# ESP8266.net
KiCad netlist of a schematic drawn in Altium Designer
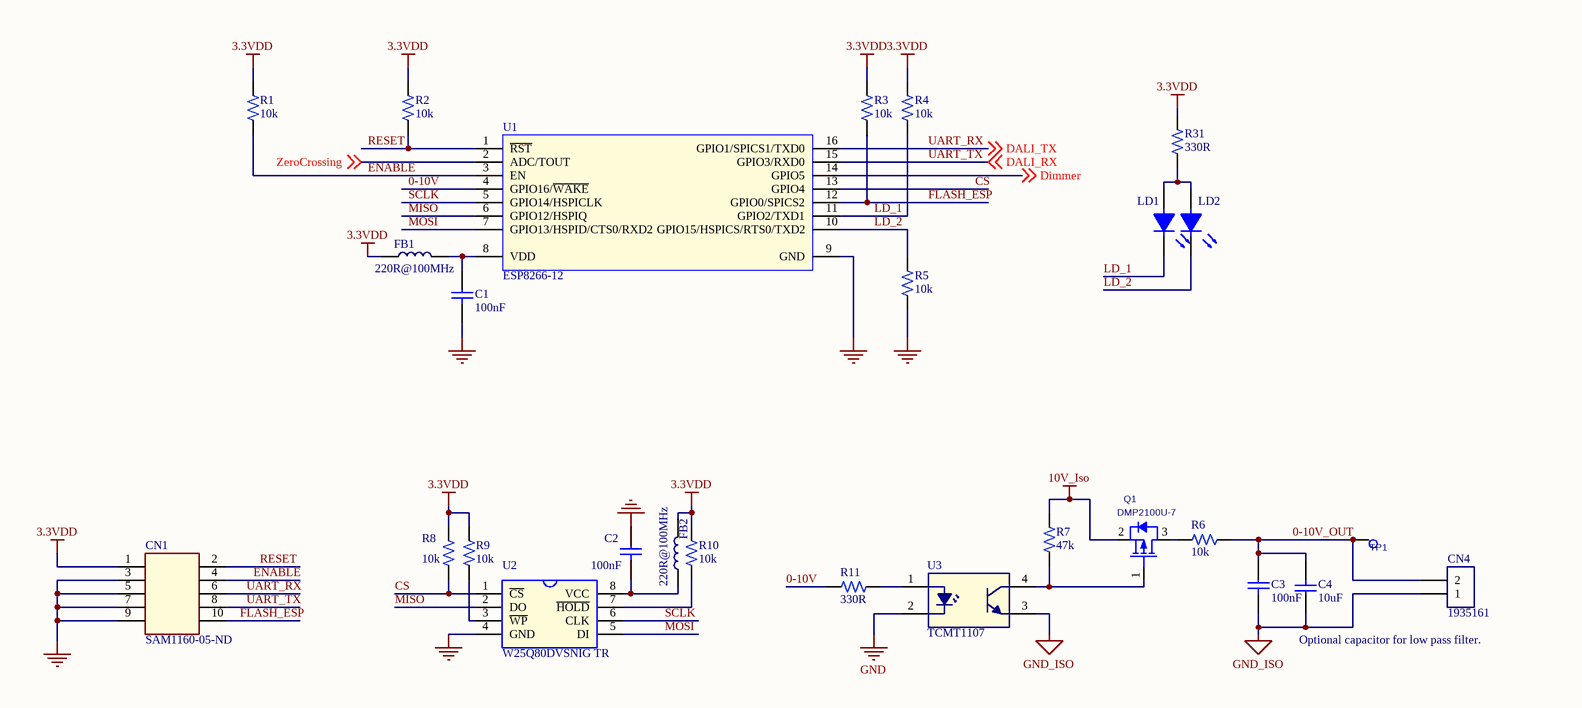
[diagram p0: ESP8266.SchDoc]

(export (version "E")
  (design (tool "Eeschema 10.0.6"))
  (components
    (comp (ref "C1")
      (value "100nF")
      (footprint "0603-3D")
      (description "CAP CER 0.1UF 50V 10% X7R 0603")
      (fields (field (name "VOLTAGE") "50V") (field (name "USER") "Anderson Daniel Soares"))
      (libsource (lib "CapacitoresPrjLib") (part "0.1uF 10% 0603 MLCC X7R 50V"))
    )
    (comp (ref "C2")
      (value "100nF")
      (footprint "0603-3D")
      (description "CAP CER 0.1UF 50V 10% X7R 0603")
      (fields (field (name "VOLTAGE") "50V") (field (name "USER") "Anderson Daniel Soares"))
      (libsource (lib "CapacitoresPrjLib") (part "0.1uF 10% 0603 MLCC X7R 50V"))
    )
    (comp (ref "C3")
      (value "100nF")
      (footprint "0603-3D")
      (description "CAP CER 0.1UF 50V 10% X7R 0603")
      (fields (field (name "VOLTAGE") "50V") (field (name "USER") "Anderson Daniel Soares"))
      (libsource (lib "CapacitoresPrjLib") (part "0.1uF 10% 0603 MLCC X7R 50V"))
    )
    (comp (ref "C4")
      (value "10uF")
      (footprint "CAP-0603-3D")
      (description "CAP CER 10UF 16V 20% X5R 0603")
      (fields (field (name "VOLTAGE") "16V") (field (name "USER") "Mateus Elias"))
      (libsource (lib "CapacitoresPrjLib") (part "10uF 20% 0603 MLCC X5R 16V"))
    )
    (comp (ref "CN1")
      (value "SAM1160-05-ND")
      (footprint "CON-SMD-MINITEK-H-2X5-127P")
      (description "10 Positions Header, Unshrouded Connector 0.050\" (1.27mm) Surface Mount, Right Angle Gold")
      (fields (field (name "USER") "Jean Pierre"))
      (libsource (lib "Conectores") (part "SAM1160-05-ND CN HDR 5X2 1.27mm 90°"))
    )
    (comp (ref "CN4")
      (value "1935161")
      (footprint "TERM BLOCK PCB 2POS 5.0MM")
      (description "TERM BLOCK PCB 2POS 5.0MM")
      (fields (field (name "USER") "Rodrigo Balbi"))
      (libsource (lib "Conectores") (part "1935161  TERM BLOCK PCB 2X1"))
    )
    (comp (ref "FB1")
      (value "220R@100MHz")
      (footprint "IND-0603-3D")
      (description "FERRITE CHIP 0603 220 OHM")
      (fields (field (name "USER") "Jean Pierre"))
      (libsource (lib "IndutoresPrjLib") (part "220R@100MHz 0603 FB 0.05R 2A"))
    )
    (comp (ref "FB2")
      (value "220R@100MHz")
      (footprint "IND-0603-3D")
      (description "FERRITE CHIP 0603 220 OHM")
      (fields (field (name "USER") "Jean Pierre"))
      (libsource (lib "IndutoresPrjLib") (part "220R@100MHz 0603 FB 0.05R 2A"))
    )
    (comp (ref "LD1")
      (value "LG R971-KN-1")
      (footprint "GREEN-LED-0805-3D")
      (description "Green 570nm LED Indication - Discrete 2.2V 0805 (2012 Metric)")
      (fields (field (name "USER") "Reis"))
      (libsource (lib "Opticos") (part "LED GREEN DIFFUSED 0805 SMD"))
    )
    (comp (ref "LD2")
      (value "LS R976-NR-1")
      (footprint "RED-LED-0805-3D")
      (description "Red 633nm LED Indication - Discrete 2V 0805 (2012 Metric)")
      (fields (field (name "USER") "Reis"))
      (libsource (lib "Opticos") (part "LED RED DIFFUSED 0805 SMD"))
    )
    (comp (ref "Q1")
      (value "DMP2100U-7")
      (footprint "SOT23-3D")
      (description "MOSFET P CH 20V 4.3A SOT23")
      (fields (field (name "USER") "Reis"))
      (libsource (lib "Transistores") (part "DMP2100U-7 MOSFET P-CH"))
    )
    (comp (ref "R1")
      (value "10k")
      (footprint "0603-3D")
      (description "RES SMD 10K OHM 1% 1/10W 0603")
      (fields
        (field (name "MANUFACTURER") "Yageo")
        (field (name "MANUFACTURER PART NUMBER") "RC0603FR-0710KL")
        (field (name "USER") "Pedro Vilela")
      )
      (libsource (lib "ResitoresPrjLib") (part "10k 1% 0603 TNF 1/10W"))
    )
    (comp (ref "R2")
      (value "10k")
      (footprint "0603-3D")
      (description "RES SMD 10K OHM 1% 1/10W 0603")
      (fields
        (field (name "MANUFACTURER") "Yageo")
        (field (name "MANUFACTURER PART NUMBER") "RC0603FR-0710KL")
        (field (name "USER") "Pedro Vilela")
      )
      (libsource (lib "ResitoresPrjLib") (part "10k 1% 0603 TNF 1/10W"))
    )
    (comp (ref "R3")
      (value "10k")
      (footprint "0603-3D")
      (description "RES SMD 10K OHM 1% 1/10W 0603")
      (fields
        (field (name "MANUFACTURER") "Yageo")
        (field (name "MANUFACTURER PART NUMBER") "RC0603FR-0710KL")
        (field (name "USER") "Pedro Vilela")
      )
      (libsource (lib "ResitoresPrjLib") (part "10k 1% 0603 TNF 1/10W"))
    )
    (comp (ref "R4")
      (value "10k")
      (footprint "0603-3D")
      (description "RES SMD 10K OHM 1% 1/10W 0603")
      (fields
        (field (name "MANUFACTURER") "Yageo")
        (field (name "MANUFACTURER PART NUMBER") "RC0603FR-0710KL")
        (field (name "USER") "Pedro Vilela")
      )
      (libsource (lib "ResitoresPrjLib") (part "10k 1% 0603 TNF 1/10W"))
    )
    (comp (ref "R5")
      (value "10k")
      (footprint "0603-3D")
      (description "RES SMD 10K OHM 1% 1/10W 0603")
      (fields
        (field (name "MANUFACTURER") "Yageo")
        (field (name "MANUFACTURER PART NUMBER") "RC0603FR-0710KL")
        (field (name "USER") "Pedro Vilela")
      )
      (libsource (lib "ResitoresPrjLib") (part "10k 1% 0603 TNF 1/10W"))
    )
    (comp (ref "R6")
      (value "10k")
      (footprint "0603-3D")
      (description "RES SMD 10K OHM 1% 1/10W 0603")
      (fields
        (field (name "MANUFACTURER") "Yageo")
        (field (name "MANUFACTURER PART NUMBER") "RC0603FR-0710KL")
        (field (name "USER") "Pedro Vilela")
      )
      (libsource (lib "ResitoresPrjLib") (part "10k 1% 0603 TNF 1/10W"))
    )
    (comp (ref "R7")
      (value "47k")
      (footprint "0603-3D")
      (description "RES SMD 47K OHM 1% 1/10W 0603")
      (fields (field (name "USER") "Anderson Daniel Soares"))
      (libsource (lib "ResitoresPrjLib") (part "47k 1% 0603 TKF 1/16W"))
    )
    (comp (ref "R8")
      (value "10k")
      (footprint "0603-3D")
      (description "RES SMD 10K OHM 1% 1/10W 0603")
      (fields
        (field (name "MANUFACTURER") "Yageo")
        (field (name "MANUFACTURER PART NUMBER") "RC0603FR-0710KL")
        (field (name "USER") "Pedro Vilela")
      )
      (libsource (lib "ResitoresPrjLib") (part "10k 1% 0603 TNF 1/10W"))
    )
    (comp (ref "R9")
      (value "10k")
      (footprint "0603-3D")
      (description "RES SMD 10K OHM 1% 1/10W 0603")
      (fields
        (field (name "MANUFACTURER") "Yageo")
        (field (name "MANUFACTURER PART NUMBER") "RC0603FR-0710KL")
        (field (name "USER") "Pedro Vilela")
      )
      (libsource (lib "ResitoresPrjLib") (part "10k 1% 0603 TNF 1/10W"))
    )
    (comp (ref "R10")
      (value "10k")
      (footprint "0603-3D")
      (description "RES SMD 10K OHM 1% 1/10W 0603")
      (fields
        (field (name "MANUFACTURER") "Yageo")
        (field (name "MANUFACTURER PART NUMBER") "RC0603FR-0710KL")
        (field (name "USER") "Pedro Vilela")
      )
      (libsource (lib "ResitoresPrjLib") (part "10k 1% 0603 TNF 1/10W"))
    )
    (comp (ref "R11")
      (value "330R")
      (footprint "0603-3D")
      (description "RES SMD 330 OHM 5% 1/10W 0603")
      (fields (field (name "TOLERANCE") "5%") (field (name "USER") "Luiz F Siecola"))
      (libsource (lib "ResitoresPrjLib") (part "330R 5% 0603 TKF 1/10W"))
    )
    (comp (ref "R31")
      (value "330R")
      (footprint "0603-3D")
      (description "RES SMD 330 OHM 5% 1/10W 0603")
      (fields (field (name "TOLERANCE") "5%") (field (name "USER") "Luiz F Siecola"))
      (libsource (lib "ResitoresPrjLib") (part "330R 5% 0603 TKF 1/10W"))
    )
    (comp (ref "TP1")
      (value "MECH TESTPOINT 1mm")
      (footprint "Fiducial smd 1mm")
      (description "Fiducial")
      (fields (field (name "USER") "Larissa"))
      (libsource (lib "DiversosPrjLib") (part "MECH TESTPOINT 1mm"))
    )
    (comp (ref "U1")
      (value "ESP8266-12")
      (footprint "ESP8266-14-3D")
      (description "ESP8266 SMT MODULE")
      (fields (field (name "USER") "Ricardo Dias"))
      (libsource (lib "LES") (part "ESP8266-12 Wi-Fi Module"))
    )
    (comp (ref "U2")
      (value "W25Q80DVSNIG TR")
      (footprint "SOIC8-3D")
      (description "IC FLASH 8MBIT 104MHZ 8SOIC")
      (fields (field (name "USER") "Ricardo Dias"))
      (libsource (lib "LES") (part "W25Q80DVSNIG TR IC FLASH 8MBIT"))
    )
    (comp (ref "U3")
      (value "TCMT1107")
      (footprint "SOP4")
      (description "OPTOISOLATOR 3.75KV TRANS 4-SOP")
      (fields (field (name "USER") "Jean Pierre"))
      (libsource (lib "Opticos") (part "TCMT1107 OPTO TRANS"))
    )
  )
  (nets
    (net (code "1") (name "/0-10V") (class "Default")
      (node (ref "R11") (pin "1") (pinfunction "1_1") (pintype "passive"))
      (node (ref "U1") (pin "4") (pinfunction "GPIO16/~{WAKE}_4") (pintype "passive"))
    )
    (net (code "2") (name "/0-10V_OUT") (class "Default")
      (node (ref "C3") (pin "1") (pinfunction "1_1") (pintype "passive"))
      (node (ref "C4") (pin "2") (pinfunction "2_2") (pintype "passive"))
      (node (ref "CN4") (pin "2") (pinfunction "2_2") (pintype "passive"))
      (node (ref "R6") (pin "1") (pinfunction "1_1") (pintype "passive"))
      (node (ref "TP1") (pin "1") (pinfunction "1_1") (pintype "passive"))
    )
    (net (code "3") (name "/CS") (class "Default")
      (node (ref "R8") (pin "1") (pinfunction "1_1") (pintype "passive"))
      (node (ref "U1") (pin "13") (pinfunction "GPIO4_13") (pintype "passive"))
      (node (ref "U2") (pin "1") (pinfunction "~{CS}_1") (pintype "passive"))
    )
    (net (code "4") (name "/ENABLE") (class "Default")
      (node (ref "CN1") (pin "4") (pinfunction "4_4") (pintype "passive"))
      (node (ref "R1") (pin "1") (pinfunction "1_1") (pintype "passive"))
      (node (ref "U1") (pin "3") (pinfunction "EN_3") (pintype "passive"))
    )
    (net (code "5") (name "/FLASH_ESP") (class "Default")
      (node (ref "CN1") (pin "10") (pinfunction "10_10") (pintype "passive"))
      (node (ref "R3") (pin "1") (pinfunction "1_1") (pintype "passive"))
      (node (ref "U1") (pin "12") (pinfunction "GPIO0/SPICS2_12") (pintype "passive"))
    )
    (net (code "6") (name "/LD_1") (class "Default")
      (node (ref "LD1") (pin "2") (pinfunction "CATODE_2") (pintype "passive"))
      (node (ref "R4") (pin "1") (pinfunction "1_1") (pintype "passive"))
      (node (ref "U1") (pin "11") (pinfunction "GPIO2/TXD1_11") (pintype "passive"))
    )
    (net (code "7") (name "/LD_2") (class "Default")
      (node (ref "LD2") (pin "2") (pinfunction "CATODE_2") (pintype "passive"))
      (node (ref "R5") (pin "2") (pinfunction "2_2") (pintype "passive"))
      (node (ref "U1") (pin "10") (pinfunction "GPIO15/HSPICS/RTS0/TXD2_10") (pintype "passive"))
    )
    (net (code "8") (name "/MISO") (class "Default")
      (node (ref "U1") (pin "6") (pinfunction "GPIO12/HSPIQ_6") (pintype "passive"))
      (node (ref "U2") (pin "2") (pinfunction "DO_2") (pintype "passive"))
    )
    (net (code "9") (name "/MOSI") (class "Default")
      (node (ref "U1") (pin "7") (pinfunction "GPIO13/HSPID/CTS0/RXD2_7") (pintype "passive"))
      (node (ref "U2") (pin "5") (pinfunction "DI_5") (pintype "passive"))
    )
    (net (code "10") (name "/RESET") (class "Default")
      (node (ref "CN1") (pin "2") (pinfunction "2_2") (pintype "passive"))
      (node (ref "R2") (pin "1") (pinfunction "1_1") (pintype "passive"))
      (node (ref "U1") (pin "1") (pinfunction "~{RST}_1") (pintype "passive"))
    )
    (net (code "11") (name "/SCLK") (class "Default")
      (node (ref "U1") (pin "5") (pinfunction "GPIO14/HSPICLK_5") (pintype "passive"))
      (node (ref "U2") (pin "6") (pinfunction "CLK_6") (pintype "passive"))
    )
    (net (code "12") (name "3.3VDD") (class "Default")
      (node (ref "CN1") (pin "1") (pinfunction "1_1") (pintype "passive"))
      (node (ref "FB1") (pin "1") (pinfunction "1_1") (pintype "passive"))
      (node (ref "FB2") (pin "2") (pinfunction "2_2") (pintype "passive"))
      (node (ref "R1") (pin "2") (pinfunction "2_2") (pintype "passive"))
      (node (ref "R10") (pin "2") (pinfunction "2_2") (pintype "passive"))
      (node (ref "R2") (pin "2") (pinfunction "2_2") (pintype "passive"))
      (node (ref "R3") (pin "2") (pinfunction "2_2") (pintype "passive"))
      (node (ref "R31") (pin "2") (pinfunction "2_2") (pintype "passive"))
      (node (ref "R4") (pin "2") (pinfunction "2_2") (pintype "passive"))
      (node (ref "R8") (pin "2") (pinfunction "2_2") (pintype "passive"))
      (node (ref "R9") (pin "2") (pinfunction "2_2") (pintype "passive"))
    )
    (net (code "13") (name "10V_Iso") (class "Default")
      (node (ref "Q1") (pin "2") (pinfunction "S_2") (pintype "passive"))
      (node (ref "R7") (pin "2") (pinfunction "2_2") (pintype "passive"))
    )
    (net (code "14") (name "DALI_RX") (class "Default")
      (node (ref "CN1") (pin "8") (pinfunction "8_8") (pintype "passive"))
      (node (ref "U1") (pin "15") (pinfunction "GPIO3/RXD0_15") (pintype "passive"))
    )
    (net (code "15") (name "DALI_TX") (class "Default")
      (node (ref "CN1") (pin "6") (pinfunction "6_6") (pintype "passive"))
      (node (ref "U1") (pin "16") (pinfunction "GPIO1/SPICS1/TXD0_16") (pintype "passive"))
    )
    (net (code "16") (name "Dimmer") (class "Default")
      (node (ref "U1") (pin "14") (pinfunction "GPIO5_14") (pintype "passive"))
    )
    (net (code "17") (name "GND") (class "Default")
      (node (ref "C1") (pin "2") (pinfunction "2_2") (pintype "passive"))
      (node (ref "C2") (pin "1") (pinfunction "1_1") (pintype "passive"))
      (node (ref "CN1") (pin "3") (pinfunction "3_3") (pintype "passive"))
      (node (ref "CN1") (pin "5") (pinfunction "5_5") (pintype "passive"))
      (node (ref "CN1") (pin "7") (pinfunction "7_7") (pintype "passive"))
      (node (ref "CN1") (pin "9") (pinfunction "9_9") (pintype "passive"))
      (node (ref "R5") (pin "1") (pinfunction "1_1") (pintype "passive"))
      (node (ref "U1") (pin "9") (pinfunction "GND_9") (pintype "passive"))
      (node (ref "U2") (pin "4") (pinfunction "GND_4") (pintype "passive"))
      (node (ref "U3") (pin "2") (pinfunction "K_2") (pintype "passive"))
    )
    (net (code "18") (name "GND_ISO") (class "Default")
      (node (ref "C3") (pin "2") (pinfunction "2_2") (pintype "passive"))
      (node (ref "C4") (pin "1") (pinfunction "1_1") (pintype "passive"))
      (node (ref "CN4") (pin "1") (pinfunction "1_1") (pintype "passive"))
      (node (ref "U3") (pin "3") (pinfunction "E_3") (pintype "passive"))
    )
    (net (code "19") (name "Net-(LD1-ANODE)") (class "Default")
      (node (ref "LD1") (pin "1") (pinfunction "ANODE_1") (pintype "passive"))
      (node (ref "LD2") (pin "1") (pinfunction "ANODE_1") (pintype "passive"))
      (node (ref "R31") (pin "1") (pinfunction "1_1") (pintype "passive"))
    )
    (net (code "20") (name "Net-(Q1-D)") (class "Default")
      (node (ref "Q1") (pin "3") (pinfunction "D_3") (pintype "passive"))
      (node (ref "R6") (pin "2") (pinfunction "2_2") (pintype "passive"))
    )
    (net (code "21") (name "Net-(Q1-G)") (class "Default")
      (node (ref "Q1") (pin "1") (pinfunction "G_1") (pintype "passive"))
      (node (ref "R7") (pin "1") (pinfunction "1_1") (pintype "passive"))
      (node (ref "U3") (pin "4") (pinfunction "C_4") (pintype "passive"))
    )
    (net (code "22") (name "Net-(U1-VDD)") (class "Default")
      (node (ref "C1") (pin "1") (pinfunction "1_1") (pintype "passive"))
      (node (ref "FB1") (pin "2") (pinfunction "2_2") (pintype "passive"))
      (node (ref "U1") (pin "8") (pinfunction "VDD_8") (pintype "passive"))
    )
    (net (code "23") (name "Net-(U2-VCC)") (class "Default")
      (node (ref "C2") (pin "2") (pinfunction "2_2") (pintype "passive"))
      (node (ref "FB2") (pin "1") (pinfunction "1_1") (pintype "passive"))
      (node (ref "U2") (pin "8") (pinfunction "VCC_8") (pintype "passive"))
    )
    (net (code "24") (name "Net-(U2-~{HOLD})") (class "Default")
      (node (ref "R10") (pin "1") (pinfunction "1_1") (pintype "passive"))
      (node (ref "U2") (pin "7") (pinfunction "~{HOLD}_7") (pintype "passive"))
    )
    (net (code "25") (name "Net-(U2-~{WP})") (class "Default")
      (node (ref "R9") (pin "1") (pinfunction "1_1") (pintype "passive"))
      (node (ref "U2") (pin "3") (pinfunction "~{WP}_3") (pintype "passive"))
    )
    (net (code "26") (name "Net-(U3-A)") (class "Default")
      (node (ref "R11") (pin "2") (pinfunction "2_2") (pintype "passive"))
      (node (ref "U3") (pin "1") (pinfunction "A_1") (pintype "passive"))
    )
    (net (code "27") (name "ZeroCrossing") (class "Default")
      (node (ref "U1") (pin "2") (pinfunction "ADC/TOUT_2") (pintype "passive"))
    )
  )
)
